# tree_io.net
KiCad netlist of a schematic drawn in Altium Designer
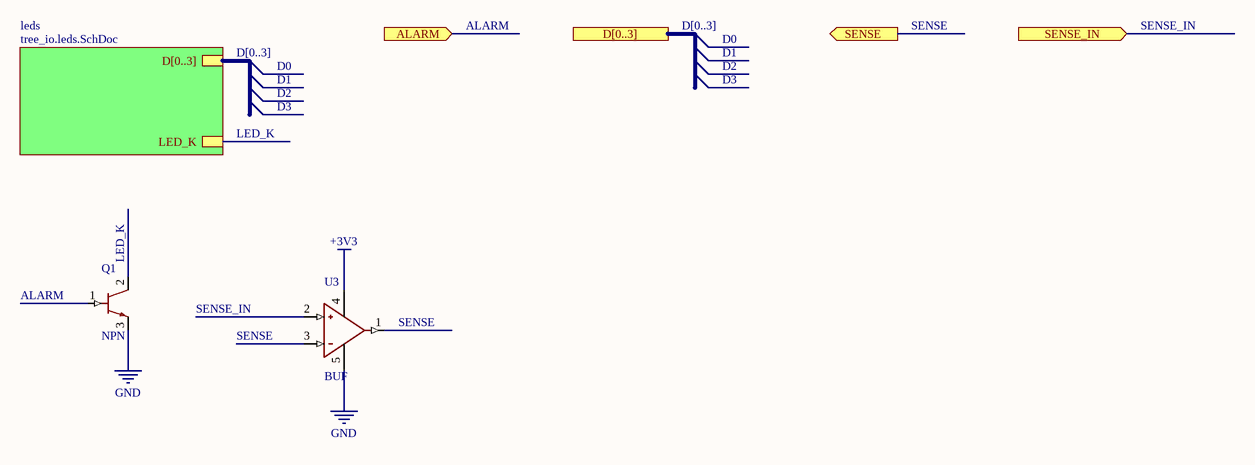
[diagram p0: tree_io.SchDoc]

(export (version "E")
  (design (tool "Eeschema 10.0.6"))
  (components
    (comp (ref "Q1") (value "NPN") (footprint "FenoliteTree:SOT23") (libsource (lib "tree") (part "BJT_NPN")))
    (comp (ref "U3")
      (value "BUF")
      (footprint "FenoliteTree:SOT23-5")
      (libsource (lib "tree") (part "Operational_Amplifier"))
    )
  )
  (nets
    (net (code "1") (name "+3V3") (class "Default")
      (node (ref "U3") (pin "4") (pinfunction "V+_4") (pintype "power_in"))
    )
    (net (code "2") (name "/ALARM") (class "Default")
      (node (ref "Q1") (pin "1") (pinfunction "B_1") (pintype "input"))
    )
    (net (code "8") (name "/LED_K") (class "Default")
      (node (ref "Q1") (pin "2") (pinfunction "C_2") (pintype "passive"))
    )
    (net (code "9") (name "/SENSE") (class "Default")
      (node (ref "U3") (pin "1") (pintype "output"))
      (node (ref "U3") (pin "3") (pinfunction "-_3") (pintype "input"))
    )
    (net (code "10") (name "/SENSE_IN") (class "Default")
      (node (ref "U3") (pin "2") (pinfunction "+_2") (pintype "input"))
    )
    (net (code "11") (name "GND") (class "Default")
      (node (ref "Q1") (pin "3") (pinfunction "E_3") (pintype "passive"))
      (node (ref "U3") (pin "5") (pinfunction "V-_5") (pintype "power_in"))
    )
  )
)
